# FusesControl.net
KiCad netlist of a schematic drawn in Altium Designer
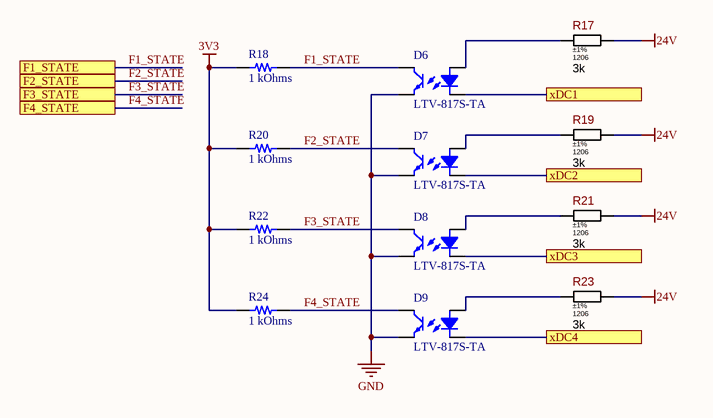
[diagram p0: FusesControl.SchDoc]

(export (version "E")
  (design (tool "Eeschema 10.0.6"))
  (components
    (comp (ref "D6")
      (value "LTV-817S-TA")
      (footprint "LITEON LTV-817")
      (description "OPTOISOLATR 5KV TRANSISTOR 4-SMD")
      (fields (field (name "MANUFACTURER") "Lite-On Inc."))
      (libsource (lib "Celestial Altium Library - altium_library") (part "Optoisolator"))
    )
    (comp (ref "D7")
      (value "LTV-817S-TA")
      (footprint "LITEON LTV-817")
      (description "OPTOISOLATR 5KV TRANSISTOR 4-SMD")
      (fields (field (name "MANUFACTURER") "Lite-On Inc."))
      (libsource (lib "Celestial Altium Library - altium_library") (part "Optoisolator"))
    )
    (comp (ref "D8")
      (value "LTV-817S-TA")
      (footprint "LITEON LTV-817")
      (description "OPTOISOLATR 5KV TRANSISTOR 4-SMD")
      (fields (field (name "MANUFACTURER") "Lite-On Inc."))
      (libsource (lib "Celestial Altium Library - altium_library") (part "Optoisolator"))
    )
    (comp (ref "D9")
      (value "LTV-817S-TA")
      (footprint "LITEON LTV-817")
      (description "OPTOISOLATR 5KV TRANSISTOR 4-SMD")
      (fields (field (name "MANUFACTURER") "Lite-On Inc."))
      (libsource (lib "Celestial Altium Library - altium_library") (part "Optoisolator"))
    )
    (comp (ref "R17")
      (value "3k")
      (footprint "R_ANY_CHIP_1206_MED")
      (description "3 kOhms ±1%, 1/4W 1206 Thick Film Resistor")
      (fields
        (field (name "TOLERANCE") "±1%")
        (field (name "PACKAGE") "1206")
        (field (name "PART NUMBER") "RC1206FR-073KL")
        (field (name "MANUFACTURER") "Yageo")
      )
      (libsource (lib "SOG.T01.PWR.621.v1_1") (part "RC1206FR-073KL"))
    )
    (comp (ref "R18")
      (value "1 kOhms")
      (footprint "RES 0805_2012")
      (description "RES 1K OHM 0.1% 1/10W 0805")
      (fields
        (field (name "PART NUMBER") "RNCS0805BKE1K00")
        (field (name "MANUFACTURER") "Stackpole Electronics Inc")
      )
      (libsource (lib "Celestial Altium Library - altium_library") (part "Resistor"))
    )
    (comp (ref "R19")
      (value "3k")
      (footprint "R_ANY_CHIP_1206_MED")
      (description "3 kOhms ±1%, 1/4W 1206 Thick Film Resistor")
      (fields
        (field (name "TOLERANCE") "±1%")
        (field (name "PACKAGE") "1206")
        (field (name "PART NUMBER") "RC1206FR-073KL")
        (field (name "MANUFACTURER") "Yageo")
      )
      (libsource (lib "SOG.T01.PWR.621.v1_1") (part "RC1206FR-073KL"))
    )
    (comp (ref "R20")
      (value "1 kOhms")
      (footprint "RES 0805_2012")
      (description "RES 1K OHM 0.1% 1/10W 0805")
      (fields
        (field (name "PART NUMBER") "RNCS0805BKE1K00")
        (field (name "MANUFACTURER") "Stackpole Electronics Inc")
      )
      (libsource (lib "Celestial Altium Library - altium_library") (part "Resistor"))
    )
    (comp (ref "R21")
      (value "3k")
      (footprint "R_ANY_CHIP_1206_MED")
      (description "3 kOhms ±1%, 1/4W 1206 Thick Film Resistor")
      (fields
        (field (name "TOLERANCE") "±1%")
        (field (name "PACKAGE") "1206")
        (field (name "PART NUMBER") "RC1206FR-073KL")
        (field (name "MANUFACTURER") "Yageo")
      )
      (libsource (lib "SOG.T01.PWR.621.v1_1") (part "RC1206FR-073KL"))
    )
    (comp (ref "R22")
      (value "1 kOhms")
      (footprint "RES 0805_2012")
      (description "RES 1K OHM 0.1% 1/10W 0805")
      (fields
        (field (name "PART NUMBER") "RNCS0805BKE1K00")
        (field (name "MANUFACTURER") "Stackpole Electronics Inc")
      )
      (libsource (lib "Celestial Altium Library - altium_library") (part "Resistor"))
    )
    (comp (ref "R23")
      (value "3k")
      (footprint "R_ANY_CHIP_1206_MED")
      (description "3 kOhms ±1%, 1/4W 1206 Thick Film Resistor")
      (fields
        (field (name "TOLERANCE") "±1%")
        (field (name "PACKAGE") "1206")
        (field (name "PART NUMBER") "RC1206FR-073KL")
        (field (name "MANUFACTURER") "Yageo")
      )
      (libsource (lib "SOG.T01.PWR.621.v1_1") (part "RC1206FR-073KL"))
    )
    (comp (ref "R24")
      (value "1 kOhms")
      (footprint "RES 0805_2012")
      (description "RES 1K OHM 0.1% 1/10W 0805")
      (fields
        (field (name "PART NUMBER") "RNCS0805BKE1K00")
        (field (name "MANUFACTURER") "Stackpole Electronics Inc")
      )
      (libsource (lib "Celestial Altium Library - altium_library") (part "Resistor"))
    )
  )
  (nets
    (net (code "1") (name "/F1_STATE") (class "Default")
      (node (ref "D6") (pin "4") (pinfunction "4_4") (pintype "passive"))
      (node (ref "R18") (pin "1") (pinfunction "1_1") (pintype "passive"))
    )
    (net (code "2") (name "/F2_STATE") (class "Default")
      (node (ref "D7") (pin "4") (pinfunction "4_4") (pintype "passive"))
      (node (ref "R20") (pin "1") (pinfunction "1_1") (pintype "passive"))
    )
    (net (code "3") (name "/F3_STATE") (class "Default")
      (node (ref "D8") (pin "4") (pinfunction "4_4") (pintype "passive"))
      (node (ref "R22") (pin "1") (pinfunction "1_1") (pintype "passive"))
    )
    (net (code "4") (name "/F4_STATE") (class "Default")
      (node (ref "D9") (pin "4") (pinfunction "4_4") (pintype "passive"))
      (node (ref "R24") (pin "1") (pinfunction "1_1") (pintype "passive"))
    )
    (net (code "5") (name "/xDC1") (class "Default")
      (node (ref "D6") (pin "2") (pinfunction "2_2") (pintype "passive"))
    )
    (net (code "6") (name "/xDC2") (class "Default")
      (node (ref "D7") (pin "2") (pinfunction "2_2") (pintype "passive"))
    )
    (net (code "7") (name "/xDC3") (class "Default")
      (node (ref "D8") (pin "2") (pinfunction "2_2") (pintype "passive"))
    )
    (net (code "8") (name "/xDC4") (class "Default")
      (node (ref "D9") (pin "2") (pinfunction "2_2") (pintype "passive"))
    )
    (net (code "9") (name "3V3") (class "Default")
      (node (ref "R18") (pin "2") (pinfunction "2_2") (pintype "passive"))
      (node (ref "R20") (pin "2") (pinfunction "2_2") (pintype "passive"))
      (node (ref "R22") (pin "2") (pinfunction "2_2") (pintype "passive"))
      (node (ref "R24") (pin "2") (pinfunction "2_2") (pintype "passive"))
    )
    (net (code "10") (name "24V") (class "Default")
      (node (ref "R17") (pin "2") (pintype "passive"))
      (node (ref "R19") (pin "2") (pintype "passive"))
      (node (ref "R21") (pin "2") (pintype "passive"))
      (node (ref "R23") (pin "2") (pintype "passive"))
    )
    (net (code "11") (name "GND") (class "Default")
      (node (ref "D6") (pin "3") (pinfunction "3_3") (pintype "passive"))
      (node (ref "D7") (pin "3") (pinfunction "3_3") (pintype "passive"))
      (node (ref "D8") (pin "3") (pinfunction "3_3") (pintype "passive"))
      (node (ref "D9") (pin "3") (pinfunction "3_3") (pintype "passive"))
    )
    (net (code "12") (name "Net-(D6-Pad1)") (class "Default")
      (node (ref "D6") (pin "1") (pinfunction "1_1") (pintype "passive"))
      (node (ref "R17") (pin "1") (pintype "passive"))
    )
    (net (code "13") (name "Net-(D7-Pad1)") (class "Default")
      (node (ref "D7") (pin "1") (pinfunction "1_1") (pintype "passive"))
      (node (ref "R19") (pin "1") (pintype "passive"))
    )
    (net (code "14") (name "Net-(D8-Pad1)") (class "Default")
      (node (ref "D8") (pin "1") (pinfunction "1_1") (pintype "passive"))
      (node (ref "R21") (pin "1") (pintype "passive"))
    )
    (net (code "15") (name "Net-(D9-Pad1)") (class "Default")
      (node (ref "D9") (pin "1") (pinfunction "1_1") (pintype "passive"))
      (node (ref "R23") (pin "1") (pintype "passive"))
    )
  )
)
